# Vbat_key.net
KiCad netlist of a schematic drawn in Altium Designer
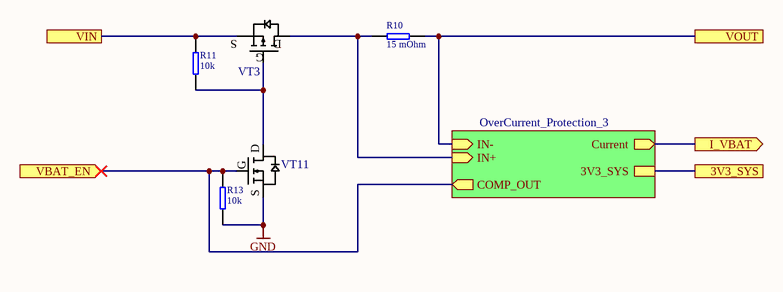
[diagram p0: Vbat_key.SchDoc]

(export (version "E")
  (design (tool "Eeschema 10.0.6"))
  (components
    (comp (ref "R10")
      (value "15 mOhm")
      (footprint "RES 1210")
      (description "Resistor")
      (fields (field (name "Comment") "RES 1210 15 mOhm"))
      (libsource (lib "!main") (part "!Resistor"))
    )
    (comp (ref "R11")
      (value "10k")
      (footprint "RES 0402")
      (description "Resistor")
      (fields (field (name "Comment") "RES 0402 10k"))
      (libsource (lib "!main") (part "!Resistor"))
    )
    (comp (ref "R13")
      (value "10k")
      (footprint "RES 0402")
      (description "Resistor")
      (fields (field (name "Comment") "RES 0402 10k"))
      (libsource (lib "!main") (part "!Resistor"))
    )
    (comp (ref "VT3")
      (value "!Generic P MOSFET")
      (footprint "DFN-8_3x3")
      (description "generic P mosfet")
      (libsource (lib "transistors") (part "!Generic P MOSFET"))
    )
    (comp (ref "VT11")
      (value "2N7002")
      (footprint "SOT23-3")
      (description "generic N mosfet")
      (libsource (lib "transistors") (part "!Generic N MOSFET"))
    )
  )
  (nets
    (net (code "2") (name "/IN+") (class "Default")
      (node (ref "R10") (pin "1") (pinfunction "11_1") (pintype "passive"))
      (node (ref "VT3") (pin "D1") (pintype "passive"))
    )
    (net (code "4") (name "/VBAT_EN") (class "Default")
      (node (ref "R13") (pin "2") (pinfunction "12_2") (pintype "passive"))
      (node (ref "VT11") (pin "G2") (pintype "passive"))
    )
    (net (code "5") (name "/VIN") (class "Default")
      (node (ref "R11") (pin "2") (pinfunction "12_2") (pintype "passive"))
      (node (ref "VT3") (pin "S1") (pintype "passive"))
    )
    (net (code "6") (name "/VOUT") (class "Default")
      (node (ref "R10") (pin "2") (pinfunction "12_2") (pintype "passive"))
    )
    (net (code "7") (name "GND") (class "Default")
      (node (ref "R13") (pin "1") (pinfunction "11_1") (pintype "passive"))
      (node (ref "VT11") (pin "S1") (pintype "passive"))
    )
    (net (code "8") (name "Net-(R11-11)") (class "Default")
      (node (ref "R11") (pin "1") (pinfunction "11_1") (pintype "passive"))
      (node (ref "VT11") (pin "D6") (pintype "passive"))
      (node (ref "VT3") (pin "G2") (pintype "passive"))
    )
  )
)
